# display-7-seg.net
KiCad netlist of a schematic drawn in EAGLE
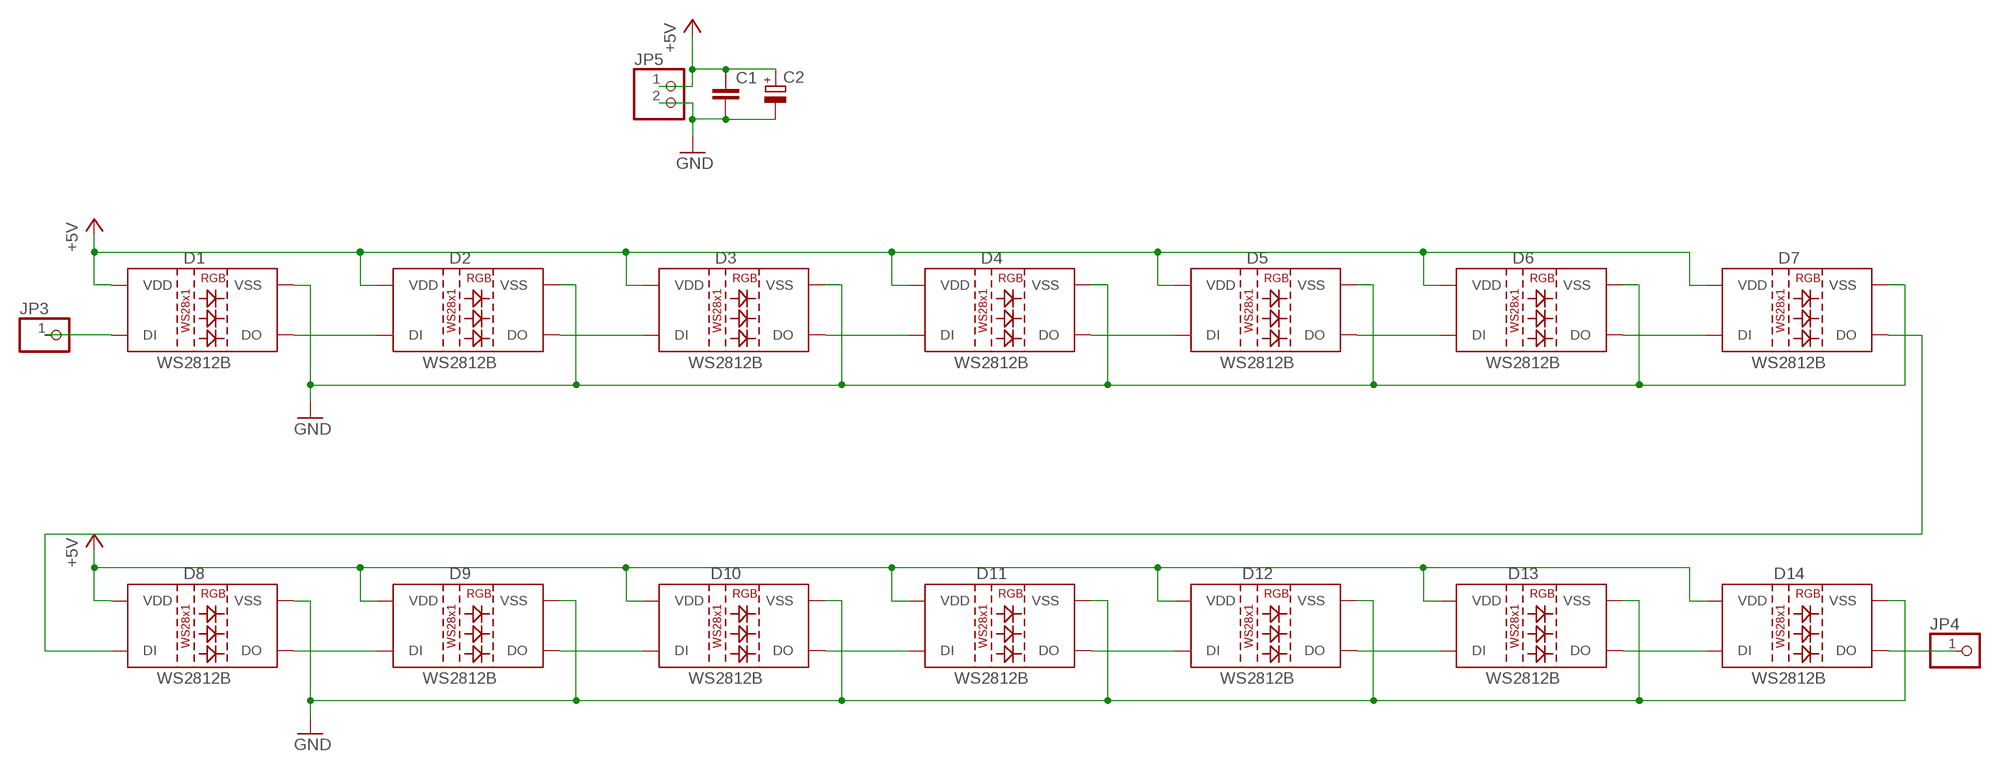
[diagram p0: schematic, sheet 1]

(export (version "E")
  (design (tool "Eeschema 10.0.6"))
  (components
    (comp (ref "C1")
      (value "C-EUC1206")
      (footprint "eagle-import:C1206")
      (libsource (lib "eagle-import") (part "C-EUC1206"))
    )
    (comp (ref "C2")
      (value "CPOL-EUE2.5-6")
      (footprint "eagle-import:E2,5-6")
      (libsource (lib "eagle-import") (part "CPOL-EUE2.5-6"))
    )
    (comp (ref "D1")
      (value "WS2812B")
      (footprint "eagle-import:WS2812B")
      (fields (field (name "MF") "Worldsemi"))
      (libsource (lib "eagle-import") (part "WS2812B"))
    )
    (comp (ref "D2")
      (value "WS2812B")
      (footprint "eagle-import:WS2812B")
      (fields (field (name "MF") "Worldsemi"))
      (libsource (lib "eagle-import") (part "WS2812B"))
    )
    (comp (ref "D3")
      (value "WS2812B")
      (footprint "eagle-import:WS2812B")
      (fields (field (name "MF") "Worldsemi"))
      (libsource (lib "eagle-import") (part "WS2812B"))
    )
    (comp (ref "D4")
      (value "WS2812B")
      (footprint "eagle-import:WS2812B")
      (fields (field (name "MF") "Worldsemi"))
      (libsource (lib "eagle-import") (part "WS2812B"))
    )
    (comp (ref "D5")
      (value "WS2812B")
      (footprint "eagle-import:WS2812B")
      (fields (field (name "MF") "Worldsemi"))
      (libsource (lib "eagle-import") (part "WS2812B"))
    )
    (comp (ref "D6")
      (value "WS2812B")
      (footprint "eagle-import:WS2812B")
      (fields (field (name "MF") "Worldsemi"))
      (libsource (lib "eagle-import") (part "WS2812B"))
    )
    (comp (ref "D7")
      (value "WS2812B")
      (footprint "eagle-import:WS2812B")
      (fields (field (name "MF") "Worldsemi"))
      (libsource (lib "eagle-import") (part "WS2812B"))
    )
    (comp (ref "D8")
      (value "WS2812B")
      (footprint "eagle-import:WS2812B")
      (fields (field (name "MF") "Worldsemi"))
      (libsource (lib "eagle-import") (part "WS2812B"))
    )
    (comp (ref "D9")
      (value "WS2812B")
      (footprint "eagle-import:WS2812B")
      (fields (field (name "MF") "Worldsemi"))
      (libsource (lib "eagle-import") (part "WS2812B"))
    )
    (comp (ref "D10")
      (value "WS2812B")
      (footprint "eagle-import:WS2812B")
      (fields (field (name "MF") "Worldsemi"))
      (libsource (lib "eagle-import") (part "WS2812B"))
    )
    (comp (ref "D11")
      (value "WS2812B")
      (footprint "eagle-import:WS2812B")
      (fields (field (name "MF") "Worldsemi"))
      (libsource (lib "eagle-import") (part "WS2812B"))
    )
    (comp (ref "D12")
      (value "WS2812B")
      (footprint "eagle-import:WS2812B")
      (fields (field (name "MF") "Worldsemi"))
      (libsource (lib "eagle-import") (part "WS2812B"))
    )
    (comp (ref "D13")
      (value "WS2812B")
      (footprint "eagle-import:WS2812B")
      (fields (field (name "MF") "Worldsemi"))
      (libsource (lib "eagle-import") (part "WS2812B"))
    )
    (comp (ref "D14")
      (value "WS2812B")
      (footprint "eagle-import:WS2812B")
      (fields (field (name "MF") "Worldsemi"))
      (libsource (lib "eagle-import") (part "WS2812B"))
    )
    (comp (ref "JP3")
      (value "PINHD-1X1")
      (footprint "eagle-import:1X01")
      (libsource (lib "eagle-import") (part "PINHD-1X1"))
    )
    (comp (ref "JP4")
      (value "PINHD-1X1")
      (footprint "eagle-import:1X01")
      (libsource (lib "eagle-import") (part "PINHD-1X1"))
    )
    (comp (ref "JP5")
      (value "PINHD-1X2")
      (footprint "eagle-import:1X02")
      (libsource (lib "eagle-import") (part "PINHD-1X2"))
    )
  )
  (nets
    (net (code "1") (name "+5V") (class "Default")
      (node (ref "C1") (pin "1") (pinfunction "1_1") (pintype "passive"))
      (node (ref "C2") (pin "+") (pinfunction "+_+") (pintype "passive"))
      (node (ref "D1") (pin "1") (pinfunction "VDD_1") (pintype "bidirectional"))
      (node (ref "D10") (pin "1") (pinfunction "VDD_1") (pintype "bidirectional"))
      (node (ref "D11") (pin "1") (pinfunction "VDD_1") (pintype "bidirectional"))
      (node (ref "D12") (pin "1") (pinfunction "VDD_1") (pintype "bidirectional"))
      (node (ref "D13") (pin "1") (pinfunction "VDD_1") (pintype "bidirectional"))
      (node (ref "D14") (pin "1") (pinfunction "VDD_1") (pintype "bidirectional"))
      (node (ref "D2") (pin "1") (pinfunction "VDD_1") (pintype "bidirectional"))
      (node (ref "D3") (pin "1") (pinfunction "VDD_1") (pintype "bidirectional"))
      (node (ref "D4") (pin "1") (pinfunction "VDD_1") (pintype "bidirectional"))
      (node (ref "D5") (pin "1") (pinfunction "VDD_1") (pintype "bidirectional"))
      (node (ref "D6") (pin "1") (pinfunction "VDD_1") (pintype "bidirectional"))
      (node (ref "D7") (pin "1") (pinfunction "VDD_1") (pintype "bidirectional"))
      (node (ref "D8") (pin "1") (pinfunction "VDD_1") (pintype "bidirectional"))
      (node (ref "D9") (pin "1") (pinfunction "VDD_1") (pintype "bidirectional"))
      (node (ref "JP5") (pin "1") (pinfunction "1_1") (pintype "passive"))
    )
    (net (code "2") (name "GND") (class "Default")
      (node (ref "C1") (pin "2") (pinfunction "2_2") (pintype "passive"))
      (node (ref "C2") (pin "-") (pinfunction "-_-") (pintype "passive"))
      (node (ref "D1") (pin "3") (pinfunction "VSS_3") (pintype "bidirectional"))
      (node (ref "D10") (pin "3") (pinfunction "VSS_3") (pintype "bidirectional"))
      (node (ref "D11") (pin "3") (pinfunction "VSS_3") (pintype "bidirectional"))
      (node (ref "D12") (pin "3") (pinfunction "VSS_3") (pintype "bidirectional"))
      (node (ref "D13") (pin "3") (pinfunction "VSS_3") (pintype "bidirectional"))
      (node (ref "D14") (pin "3") (pinfunction "VSS_3") (pintype "bidirectional"))
      (node (ref "D2") (pin "3") (pinfunction "VSS_3") (pintype "bidirectional"))
      (node (ref "D3") (pin "3") (pinfunction "VSS_3") (pintype "bidirectional"))
      (node (ref "D4") (pin "3") (pinfunction "VSS_3") (pintype "bidirectional"))
      (node (ref "D5") (pin "3") (pinfunction "VSS_3") (pintype "bidirectional"))
      (node (ref "D6") (pin "3") (pinfunction "VSS_3") (pintype "bidirectional"))
      (node (ref "D7") (pin "3") (pinfunction "VSS_3") (pintype "bidirectional"))
      (node (ref "D8") (pin "3") (pinfunction "VSS_3") (pintype "bidirectional"))
      (node (ref "D9") (pin "3") (pinfunction "VSS_3") (pintype "bidirectional"))
      (node (ref "JP5") (pin "2") (pinfunction "2_2") (pintype "passive"))
    )
    (net (code "3") (name "Net-(D1-DI)") (class "Default")
      (node (ref "D1") (pin "4") (pinfunction "DI_4") (pintype "bidirectional"))
      (node (ref "JP3") (pin "1") (pinfunction "1_1") (pintype "passive"))
    )
    (net (code "4") (name "Net-(D1-DO)") (class "Default")
      (node (ref "D1") (pin "2") (pinfunction "DO_2") (pintype "bidirectional"))
      (node (ref "D2") (pin "4") (pinfunction "DI_4") (pintype "bidirectional"))
    )
    (net (code "5") (name "Net-(D2-DO)") (class "Default")
      (node (ref "D2") (pin "2") (pinfunction "DO_2") (pintype "bidirectional"))
      (node (ref "D3") (pin "4") (pinfunction "DI_4") (pintype "bidirectional"))
    )
    (net (code "6") (name "Net-(D3-DO)") (class "Default")
      (node (ref "D3") (pin "2") (pinfunction "DO_2") (pintype "bidirectional"))
      (node (ref "D4") (pin "4") (pinfunction "DI_4") (pintype "bidirectional"))
    )
    (net (code "7") (name "Net-(D4-DO)") (class "Default")
      (node (ref "D4") (pin "2") (pinfunction "DO_2") (pintype "bidirectional"))
      (node (ref "D5") (pin "4") (pinfunction "DI_4") (pintype "bidirectional"))
    )
    (net (code "8") (name "Net-(D5-DO)") (class "Default")
      (node (ref "D5") (pin "2") (pinfunction "DO_2") (pintype "bidirectional"))
      (node (ref "D6") (pin "4") (pinfunction "DI_4") (pintype "bidirectional"))
    )
    (net (code "9") (name "Net-(D6-DO)") (class "Default")
      (node (ref "D6") (pin "2") (pinfunction "DO_2") (pintype "bidirectional"))
      (node (ref "D7") (pin "4") (pinfunction "DI_4") (pintype "bidirectional"))
    )
    (net (code "10") (name "Net-(D7-DO)") (class "Default")
      (node (ref "D7") (pin "2") (pinfunction "DO_2") (pintype "bidirectional"))
      (node (ref "D8") (pin "4") (pinfunction "DI_4") (pintype "bidirectional"))
    )
    (net (code "11") (name "Net-(D8-DO)") (class "Default")
      (node (ref "D8") (pin "2") (pinfunction "DO_2") (pintype "bidirectional"))
      (node (ref "D9") (pin "4") (pinfunction "DI_4") (pintype "bidirectional"))
    )
    (net (code "12") (name "Net-(D10-DI)") (class "Default")
      (node (ref "D10") (pin "4") (pinfunction "DI_4") (pintype "bidirectional"))
      (node (ref "D9") (pin "2") (pinfunction "DO_2") (pintype "bidirectional"))
    )
    (net (code "13") (name "Net-(D10-DO)") (class "Default")
      (node (ref "D10") (pin "2") (pinfunction "DO_2") (pintype "bidirectional"))
      (node (ref "D11") (pin "4") (pinfunction "DI_4") (pintype "bidirectional"))
    )
    (net (code "14") (name "Net-(D11-DO)") (class "Default")
      (node (ref "D11") (pin "2") (pinfunction "DO_2") (pintype "bidirectional"))
      (node (ref "D12") (pin "4") (pinfunction "DI_4") (pintype "bidirectional"))
    )
    (net (code "15") (name "Net-(D12-DO)") (class "Default")
      (node (ref "D12") (pin "2") (pinfunction "DO_2") (pintype "bidirectional"))
      (node (ref "D13") (pin "4") (pinfunction "DI_4") (pintype "bidirectional"))
    )
    (net (code "16") (name "Net-(D13-DO)") (class "Default")
      (node (ref "D13") (pin "2") (pinfunction "DO_2") (pintype "bidirectional"))
      (node (ref "D14") (pin "4") (pinfunction "DI_4") (pintype "bidirectional"))
    )
    (net (code "17") (name "Net-(D14-DO)") (class "Default")
      (node (ref "D14") (pin "2") (pinfunction "DO_2") (pintype "bidirectional"))
      (node (ref "JP4") (pin "1") (pinfunction "1_1") (pintype "passive"))
    )
  )
)
